# BPSD.net
KiCad netlist of a schematic drawn in EAGLE
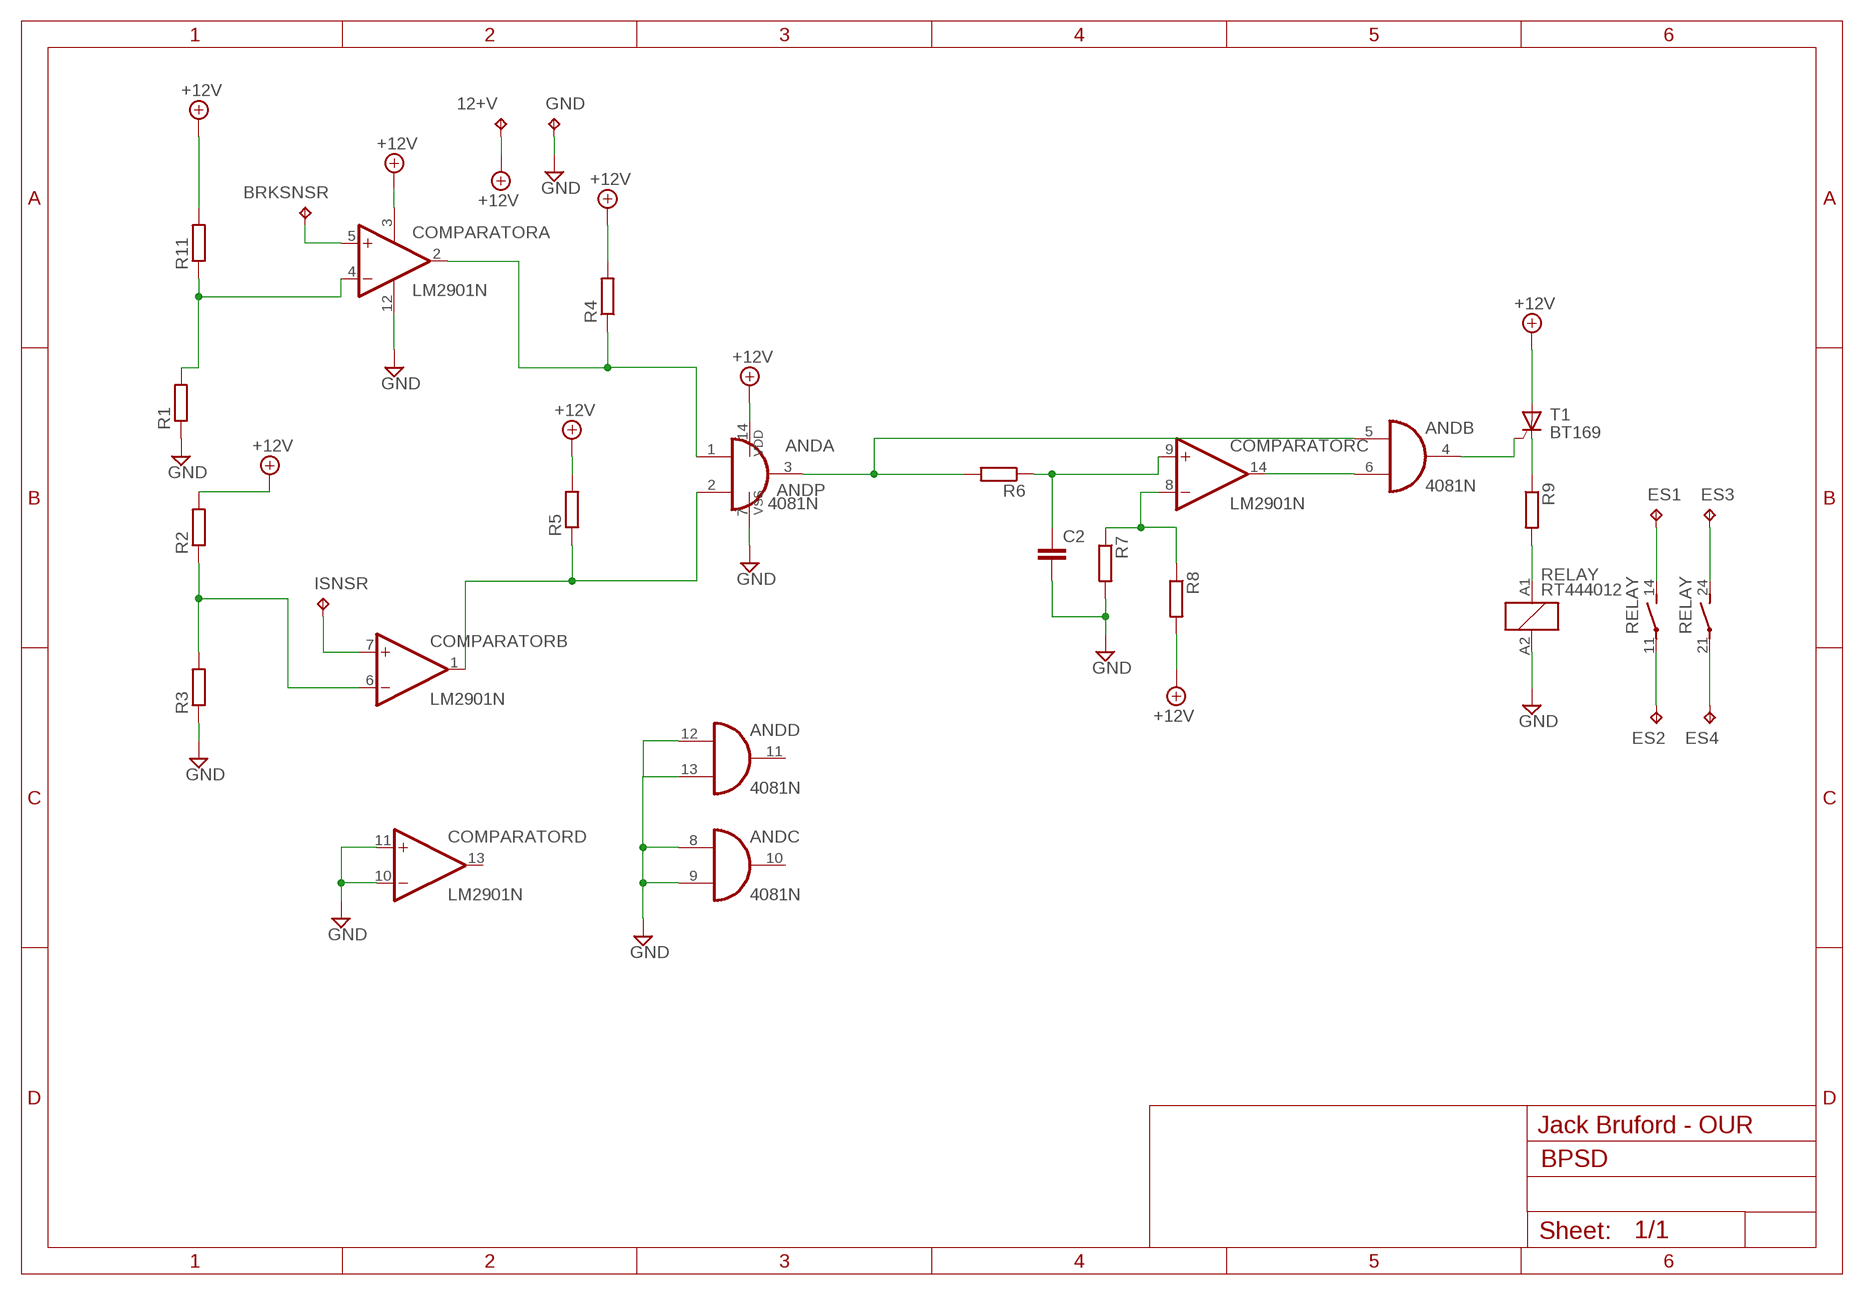
[diagram p0: schematic, sheet 1]

(export (version "E")
  (design (tool "Eeschema 10.0.6"))
  (components
    (comp (ref "12+V")
      (value "TPPAD1-13")
      (footprint "eagle-import:P1-13")
      (libsource (lib "eagle-import") (part "TPPAD1-13"))
    )
    (comp (ref "AND")
      (value "4081N")
      (footprint "eagle-import:DIL14")
      (libsource (lib "eagle-import") (part "4081N"))
    )
    (comp (ref "BRKSNSR")
      (value "TPPAD1-13")
      (footprint "eagle-import:P1-13")
      (libsource (lib "eagle-import") (part "TPPAD1-13"))
    )
    (comp (ref "C2")
      (value "C-EU050-024X044")
      (footprint "eagle-import:C050-024X044")
      (libsource (lib "eagle-import") (part "C-EU050-024X044"))
    )
    (comp (ref "COMPARATOR")
      (value "LM2901N")
      (footprint "eagle-import:DIL14")
      (libsource (lib "eagle-import") (part "LM2901N"))
    )
    (comp (ref "ES1")
      (value "TPPAD1-13")
      (footprint "eagle-import:P1-13")
      (libsource (lib "eagle-import") (part "TPPAD1-13"))
    )
    (comp (ref "ES2")
      (value "TPPAD1-13")
      (footprint "eagle-import:P1-13")
      (libsource (lib "eagle-import") (part "TPPAD1-13"))
    )
    (comp (ref "ES3")
      (value "TPPAD1-13")
      (footprint "eagle-import:P1-13")
      (libsource (lib "eagle-import") (part "TPPAD1-13"))
    )
    (comp (ref "ES4")
      (value "TPPAD1-13")
      (footprint "eagle-import:P1-13")
      (libsource (lib "eagle-import") (part "TPPAD1-13"))
    )
    (comp (ref "GND")
      (value "TPPAD1-13")
      (footprint "eagle-import:P1-13")
      (libsource (lib "eagle-import") (part "TPPAD1-13"))
    )
    (comp (ref "ISNSR")
      (value "TPPAD1-13")
      (footprint "eagle-import:P1-13")
      (libsource (lib "eagle-import") (part "TPPAD1-13"))
    )
    (comp (ref "R1")
      (value "R-EU_0207/15")
      (footprint "eagle-import:0207_15")
      (libsource (lib "eagle-import") (part "R-EU_0207/15"))
    )
    (comp (ref "R2")
      (value "R-EU_0207/15")
      (footprint "eagle-import:0207_15")
      (libsource (lib "eagle-import") (part "R-EU_0207/15"))
    )
    (comp (ref "R3")
      (value "R-EU_0207/15")
      (footprint "eagle-import:0207_15")
      (libsource (lib "eagle-import") (part "R-EU_0207/15"))
    )
    (comp (ref "R4")
      (value "R-EU_0207/15")
      (footprint "eagle-import:0207_15")
      (libsource (lib "eagle-import") (part "R-EU_0207/15"))
    )
    (comp (ref "R5")
      (value "R-EU_0207/15")
      (footprint "eagle-import:0207_15")
      (libsource (lib "eagle-import") (part "R-EU_0207/15"))
    )
    (comp (ref "R6")
      (value "R-EU_0207/15")
      (footprint "eagle-import:0207_15")
      (libsource (lib "eagle-import") (part "R-EU_0207/15"))
    )
    (comp (ref "R7")
      (value "R-EU_0207/15")
      (footprint "eagle-import:0207_15")
      (libsource (lib "eagle-import") (part "R-EU_0207/15"))
    )
    (comp (ref "R8")
      (value "R-EU_0207/15")
      (footprint "eagle-import:0207_15")
      (libsource (lib "eagle-import") (part "R-EU_0207/15"))
    )
    (comp (ref "R9")
      (value "R-EU_0207/15")
      (footprint "eagle-import:0207_15")
      (libsource (lib "eagle-import") (part "R-EU_0207/15"))
    )
    (comp (ref "R11")
      (value "R-EU_0207/15")
      (footprint "eagle-import:0207_15")
      (libsource (lib "eagle-import") (part "R-EU_0207/15"))
    )
    (comp (ref "RELAY")
      (value "RT444012")
      (footprint "eagle-import:RT2N_O")
      (libsource (lib "eagle-import") (part "RT44?4012"))
    )
    (comp (ref "T1")
      (value "BT169")
      (footprint "eagle-import:TO92-2")
      (libsource (lib "eagle-import") (part "BT169"))
    )
  )
  (nets
    (net (code "1") (name "+12V") (class "Default")
      (node (ref "12+V") (pin "TP") (pinfunction "TP_TP") (pintype "input"))
      (node (ref "AND") (pin "14") (pinfunction "VDD_14") (pintype "power_in"))
      (node (ref "COMPARATOR") (pin "3") (pinfunction "V+_3") (pintype "power_in"))
      (node (ref "R11") (pin "2") (pinfunction "2_2") (pintype "passive"))
      (node (ref "R2") (pin "2") (pinfunction "2_2") (pintype "passive"))
      (node (ref "R4") (pin "2") (pinfunction "2_2") (pintype "passive"))
      (node (ref "R5") (pin "2") (pinfunction "2_2") (pintype "passive"))
      (node (ref "R8") (pin "2") (pinfunction "2_2") (pintype "passive"))
      (node (ref "T1") (pin "A") (pinfunction "A_A") (pintype "passive"))
    )
    (net (code "2") (name "GND") (class "Default")
      (node (ref "AND") (pin "12") (pinfunction "I0_12") (pintype "input"))
      (node (ref "AND") (pin "13") (pinfunction "I1_13") (pintype "input"))
      (node (ref "AND") (pin "7") (pinfunction "VSS_7") (pintype "power_in"))
      (node (ref "AND") (pin "8") (pinfunction "I0_8") (pintype "input"))
      (node (ref "AND") (pin "9") (pinfunction "I1_9") (pintype "input"))
      (node (ref "C2") (pin "2") (pinfunction "2_2") (pintype "passive"))
      (node (ref "COMPARATOR") (pin "10") (pinfunction "-IN_10") (pintype "input"))
      (node (ref "COMPARATOR") (pin "11") (pinfunction "+IN_11") (pintype "input"))
      (node (ref "COMPARATOR") (pin "12") (pinfunction "V-_12") (pintype "power_in"))
      (node (ref "GND") (pin "TP") (pinfunction "TP_TP") (pintype "input"))
      (node (ref "R1") (pin "1") (pinfunction "1_1") (pintype "passive"))
      (node (ref "R3") (pin "1") (pinfunction "1_1") (pintype "passive"))
      (node (ref "R7") (pin "2") (pinfunction "2_2") (pintype "passive"))
      (node (ref "RELAY") (pin "A2") (pinfunction "2_A2") (pintype "passive"))
    )
    (net (code "3") (name "Net-(ANDA-I0)") (class "Default")
      (node (ref "AND") (pin "1") (pinfunction "I0_1") (pintype "input"))
      (node (ref "COMPARATOR") (pin "2") (pinfunction "OUT_2") (pintype "output"))
      (node (ref "R4") (pin "1") (pinfunction "1_1") (pintype "passive"))
    )
    (net (code "4") (name "Net-(ANDA-I1)") (class "Default")
      (node (ref "AND") (pin "2") (pinfunction "I1_2") (pintype "input"))
      (node (ref "COMPARATOR") (pin "1") (pinfunction "OUT_1") (pintype "output"))
      (node (ref "R5") (pin "1") (pinfunction "1_1") (pintype "passive"))
    )
    (net (code "5") (name "Net-(ANDA-O)") (class "Default")
      (node (ref "AND") (pin "3") (pinfunction "O_3") (pintype "output"))
      (node (ref "AND") (pin "5") (pinfunction "I0_5") (pintype "input"))
      (node (ref "R6") (pin "2") (pinfunction "2_2") (pintype "passive"))
    )
    (net (code "6") (name "Net-(ANDB-I1)") (class "Default")
      (node (ref "AND") (pin "6") (pinfunction "I1_6") (pintype "input"))
      (node (ref "COMPARATOR") (pin "14") (pinfunction "OUT_14") (pintype "output"))
    )
    (net (code "7") (name "Net-(ANDB-O)") (class "Default")
      (node (ref "AND") (pin "4") (pinfunction "O_4") (pintype "output"))
      (node (ref "T1") (pin "G") (pinfunction "G_G") (pintype "passive"))
    )
    (net (code "8") (name "Net-(COMPARATORA-+IN)") (class "Default")
      (node (ref "BRKSNSR") (pin "TP") (pinfunction "TP_TP") (pintype "input"))
      (node (ref "COMPARATOR") (pin "5") (pinfunction "+IN_5") (pintype "input"))
    )
    (net (code "9") (name "Net-(COMPARATORA--IN)") (class "Default")
      (node (ref "COMPARATOR") (pin "4") (pinfunction "-IN_4") (pintype "input"))
      (node (ref "R1") (pin "2") (pinfunction "2_2") (pintype "passive"))
      (node (ref "R11") (pin "1") (pinfunction "1_1") (pintype "passive"))
    )
    (net (code "10") (name "Net-(COMPARATORB-+IN)") (class "Default")
      (node (ref "COMPARATOR") (pin "7") (pinfunction "+IN_7") (pintype "input"))
      (node (ref "ISNSR") (pin "TP") (pinfunction "TP_TP") (pintype "input"))
    )
    (net (code "11") (name "Net-(COMPARATORB--IN)") (class "Default")
      (node (ref "COMPARATOR") (pin "6") (pinfunction "-IN_6") (pintype "input"))
      (node (ref "R2") (pin "1") (pinfunction "1_1") (pintype "passive"))
      (node (ref "R3") (pin "2") (pinfunction "2_2") (pintype "passive"))
    )
    (net (code "12") (name "Net-(COMPARATORC-+IN)") (class "Default")
      (node (ref "C2") (pin "1") (pinfunction "1_1") (pintype "passive"))
      (node (ref "COMPARATOR") (pin "9") (pinfunction "+IN_9") (pintype "input"))
      (node (ref "R6") (pin "1") (pinfunction "1_1") (pintype "passive"))
    )
    (net (code "13") (name "Net-(COMPARATORC--IN)") (class "Default")
      (node (ref "COMPARATOR") (pin "8") (pinfunction "-IN_8") (pintype "input"))
      (node (ref "R7") (pin "1") (pinfunction "1_1") (pintype "passive"))
      (node (ref "R8") (pin "1") (pinfunction "1_1") (pintype "passive"))
    )
    (net (code "14") (name "Net-(R9-Pad1)") (class "Default")
      (node (ref "R9") (pin "1") (pinfunction "1_1") (pintype "passive"))
      (node (ref "T1") (pin "C") (pinfunction "C_C") (pintype "passive"))
    )
    (net (code "15") (name "Net-(RELAYA-1)") (class "Default")
      (node (ref "R9") (pin "2") (pinfunction "2_2") (pintype "passive"))
      (node (ref "RELAY") (pin "A1") (pinfunction "1_A1") (pintype "passive"))
    )
    (net (code "16") (name "Net-(RELAYB-P)") (class "Default")
      (node (ref "ES2") (pin "TP") (pinfunction "TP_TP") (pintype "input"))
      (node (ref "RELAY") (pin "11") (pinfunction "P_11") (pintype "passive"))
    )
    (net (code "17") (name "Net-(RELAYB-S)") (class "Default")
      (node (ref "ES1") (pin "TP") (pinfunction "TP_TP") (pintype "input"))
      (node (ref "RELAY") (pin "14") (pinfunction "S_14") (pintype "passive"))
    )
    (net (code "18") (name "Net-(RELAYC-P)") (class "Default")
      (node (ref "ES4") (pin "TP") (pinfunction "TP_TP") (pintype "input"))
      (node (ref "RELAY") (pin "21") (pinfunction "P_21") (pintype "passive"))
    )
    (net (code "19") (name "Net-(RELAYC-S)") (class "Default")
      (node (ref "ES3") (pin "TP") (pinfunction "TP_TP") (pintype "input"))
      (node (ref "RELAY") (pin "24") (pinfunction "S_24") (pintype "passive"))
    )
    (net (code "20") (name "unconnected-(ANDC-O-Pad10)") (class "Default")
      (node (ref "AND") (pin "10") (pinfunction "O_10") (pintype "output"))
    )
    (net (code "21") (name "unconnected-(ANDD-O-Pad11)") (class "Default")
      (node (ref "AND") (pin "11") (pinfunction "O_11") (pintype "output"))
    )
    (net (code "22") (name "unconnected-(COMPARATORD-OUT-Pad13)") (class "Default")
      (node (ref "COMPARATOR") (pin "13") (pinfunction "OUT_13") (pintype "output"))
    )
  )
)
